# CCLoad.net
KiCad netlist of a schematic drawn in EAGLE
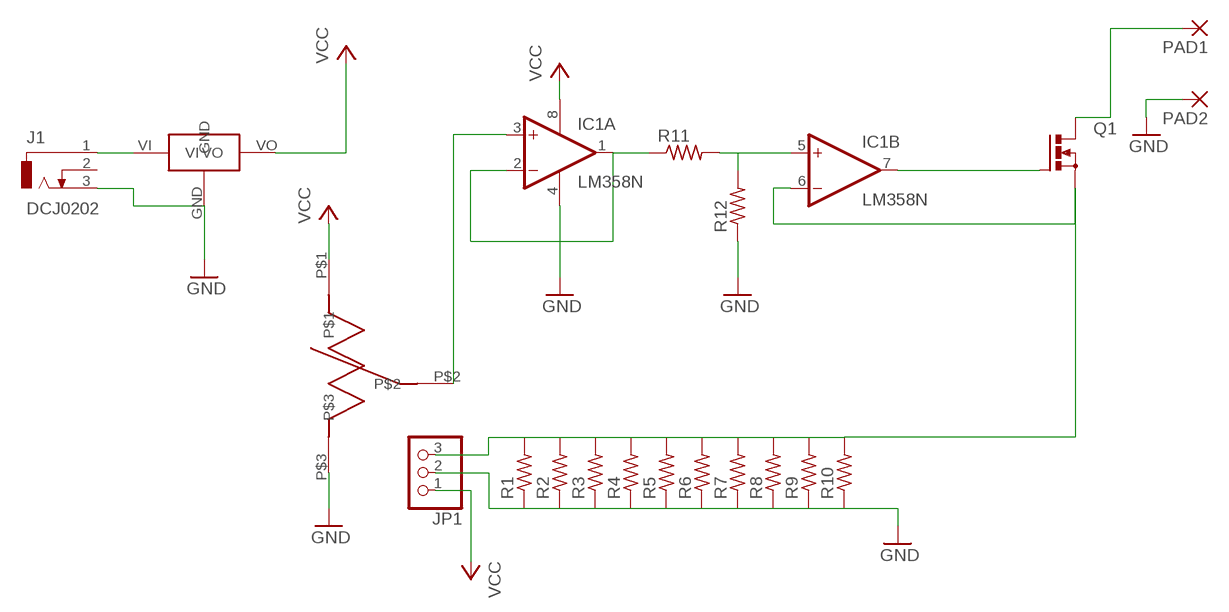
[diagram p0: schematic, sheet 1]

(export (version "E")
  (design (tool "Eeschema 10.0.6"))
  (components
    (comp (ref "IC1")
      (value "LM358N")
      (footprint "eagle-import:DIL08")
      (libsource (lib "eagle-import") (part "LM358N"))
    )
    (comp (ref "J1")
      (value "DCJ0202")
      (footprint "eagle-import:DCJ0202")
      (libsource (lib "eagle-import") (part "DCJ0202"))
    )
    (comp (ref "JP1")
      (value "PINHD-1X3")
      (footprint "eagle-import:1X03")
      (libsource (lib "eagle-import") (part "PINHD-1X3"))
    )
    (comp (ref "PAD1")
      (value "3,17/1,3")
      (footprint "eagle-import:3,17_1,3")
      (libsource (lib "eagle-import") (part "3,17/1,3"))
    )
    (comp (ref "PAD2")
      (value "3,17/1,3")
      (footprint "eagle-import:3,17_1,3")
      (libsource (lib "eagle-import") (part "3,17/1,3"))
    )
    (comp (ref "Q1")
      (value "PMOSFET_NTO220BV")
      (footprint "eagle-import:TO220BV")
      (libsource (lib "eagle-import") (part "PMOSFET_NTO220BV"))
    )
    (comp (ref "R1")
      (value "R-US_0207/10")
      (footprint "eagle-import:0207_10")
      (libsource (lib "eagle-import") (part "R-US_0207/10"))
    )
    (comp (ref "R2")
      (value "R-US_0207/10")
      (footprint "eagle-import:0207_10")
      (libsource (lib "eagle-import") (part "R-US_0207/10"))
    )
    (comp (ref "R3")
      (value "R-US_0207/10")
      (footprint "eagle-import:0207_10")
      (libsource (lib "eagle-import") (part "R-US_0207/10"))
    )
    (comp (ref "R4")
      (value "R-US_0207/10")
      (footprint "eagle-import:0207_10")
      (libsource (lib "eagle-import") (part "R-US_0207/10"))
    )
    (comp (ref "R5")
      (value "R-US_0207/10")
      (footprint "eagle-import:0207_10")
      (libsource (lib "eagle-import") (part "R-US_0207/10"))
    )
    (comp (ref "R6")
      (value "R-US_0207/10")
      (footprint "eagle-import:0207_10")
      (libsource (lib "eagle-import") (part "R-US_0207/10"))
    )
    (comp (ref "R7")
      (value "R-US_0207/10")
      (footprint "eagle-import:0207_10")
      (libsource (lib "eagle-import") (part "R-US_0207/10"))
    )
    (comp (ref "R8")
      (value "R-US_0207/10")
      (footprint "eagle-import:0207_10")
      (libsource (lib "eagle-import") (part "R-US_0207/10"))
    )
    (comp (ref "R9")
      (value "R-US_0207/10")
      (footprint "eagle-import:0207_10")
      (libsource (lib "eagle-import") (part "R-US_0207/10"))
    )
    (comp (ref "R10")
      (value "R-US_0207/10")
      (footprint "eagle-import:0207_10")
      (libsource (lib "eagle-import") (part "R-US_0207/10"))
    )
    (comp (ref "R11")
      (value "R-US_0207/10")
      (footprint "eagle-import:0207_10")
      (libsource (lib "eagle-import") (part "R-US_0207/10"))
    )
    (comp (ref "R12")
      (value "R-US_0207/10")
      (footprint "eagle-import:0207_10")
      (libsource (lib "eagle-import") (part "R-US_0207/10"))
    )
    (comp (ref "U$1")
      (value "3590")
      (footprint "eagle-import:3590")
      (libsource (lib "eagle-import") (part "3590"))
    )
    (comp (ref "U$3")
      (value "7805-TO220V")
      (footprint "eagle-import:TO220AV")
      (libsource (lib "eagle-import") (part "7805-TO220V"))
    )
  )
  (nets
    (net (code "1") (name "GND") (class "Default")
      (node (ref "IC1") (pin "4") (pinfunction "V-_4") (pintype "power_in"))
      (node (ref "J1") (pin "3") (pinfunction "3_3") (pintype "passive"))
      (node (ref "JP1") (pin "2") (pinfunction "2_2") (pintype "passive"))
      (node (ref "PAD2") (pin "1") (pinfunction "P_1") (pintype "passive"))
      (node (ref "R1") (pin "1") (pinfunction "1_1") (pintype "passive"))
      (node (ref "R10") (pin "1") (pinfunction "1_1") (pintype "passive"))
      (node (ref "R12") (pin "1") (pinfunction "1_1") (pintype "passive"))
      (node (ref "R2") (pin "1") (pinfunction "1_1") (pintype "passive"))
      (node (ref "R3") (pin "1") (pinfunction "1_1") (pintype "passive"))
      (node (ref "R4") (pin "1") (pinfunction "1_1") (pintype "passive"))
      (node (ref "R5") (pin "1") (pinfunction "1_1") (pintype "passive"))
      (node (ref "R6") (pin "1") (pinfunction "1_1") (pintype "passive"))
      (node (ref "R7") (pin "1") (pinfunction "1_1") (pintype "passive"))
      (node (ref "R8") (pin "1") (pinfunction "1_1") (pintype "passive"))
      (node (ref "R9") (pin "1") (pinfunction "1_1") (pintype "passive"))
      (node (ref "U$1") (pin "P$3") (pinfunction "P$3_P$3") (pintype "bidirectional"))
      (node (ref "U$3") (pin "GND") (pinfunction "GND_GND") (pintype "bidirectional"))
    )
    (net (code "2") (name "Net-(IC1A-+IN)") (class "Default")
      (node (ref "IC1") (pin "3") (pinfunction "+IN_3") (pintype "input"))
      (node (ref "U$1") (pin "P$2") (pinfunction "P$2_P$2") (pintype "bidirectional"))
    )
    (net (code "3") (name "Net-(IC1A--IN)") (class "Default")
      (node (ref "IC1") (pin "1") (pinfunction "OUT_1") (pintype "output"))
      (node (ref "IC1") (pin "2") (pinfunction "-IN_2") (pintype "input"))
      (node (ref "R11") (pin "1") (pinfunction "1_1") (pintype "passive"))
    )
    (net (code "4") (name "Net-(IC1B-+IN)") (class "Default")
      (node (ref "IC1") (pin "5") (pinfunction "+IN_5") (pintype "input"))
      (node (ref "R11") (pin "2") (pinfunction "2_2") (pintype "passive"))
      (node (ref "R12") (pin "2") (pinfunction "2_2") (pintype "passive"))
    )
    (net (code "5") (name "Net-(IC1B--IN)") (class "Default")
      (node (ref "IC1") (pin "6") (pinfunction "-IN_6") (pintype "input"))
      (node (ref "JP1") (pin "3") (pinfunction "3_3") (pintype "passive"))
      (node (ref "Q1") (pin "S") (pinfunction "S_S") (pintype "passive"))
      (node (ref "R1") (pin "2") (pinfunction "2_2") (pintype "passive"))
      (node (ref "R10") (pin "2") (pinfunction "2_2") (pintype "passive"))
      (node (ref "R2") (pin "2") (pinfunction "2_2") (pintype "passive"))
      (node (ref "R3") (pin "2") (pinfunction "2_2") (pintype "passive"))
      (node (ref "R4") (pin "2") (pinfunction "2_2") (pintype "passive"))
      (node (ref "R5") (pin "2") (pinfunction "2_2") (pintype "passive"))
      (node (ref "R6") (pin "2") (pinfunction "2_2") (pintype "passive"))
      (node (ref "R7") (pin "2") (pinfunction "2_2") (pintype "passive"))
      (node (ref "R8") (pin "2") (pinfunction "2_2") (pintype "passive"))
      (node (ref "R9") (pin "2") (pinfunction "2_2") (pintype "passive"))
    )
    (net (code "6") (name "Net-(IC1B-OUT)") (class "Default")
      (node (ref "IC1") (pin "7") (pinfunction "OUT_7") (pintype "output"))
      (node (ref "Q1") (pin "G") (pinfunction "G_G") (pintype "passive"))
    )
    (net (code "7") (name "Net-(J1-Pad1)") (class "Default")
      (node (ref "J1") (pin "1") (pinfunction "1_1") (pintype "passive"))
      (node (ref "U$3") (pin "VI") (pinfunction "VI_VI") (pintype "input"))
    )
    (net (code "8") (name "Net-(PAD1-P)") (class "Default")
      (node (ref "PAD1") (pin "1") (pinfunction "P_1") (pintype "passive"))
      (node (ref "Q1") (pin "D") (pinfunction "D_D") (pintype "passive"))
    )
    (net (code "9") (name "VCC") (class "Default")
      (node (ref "IC1") (pin "8") (pinfunction "V+_8") (pintype "power_in"))
      (node (ref "JP1") (pin "1") (pinfunction "1_1") (pintype "passive"))
      (node (ref "U$1") (pin "P$1") (pinfunction "P$1_P$1") (pintype "bidirectional"))
      (node (ref "U$3") (pin "VO") (pinfunction "VO_VO") (pintype "output"))
    )
    (net (code "10") (name "unconnected-(J1-Pad2)") (class "Default")
      (node (ref "J1") (pin "2") (pinfunction "2_2") (pintype "passive"))
    )
  )
)
